# M208X.net
KiCad netlist of a schematic drawn in EAGLE
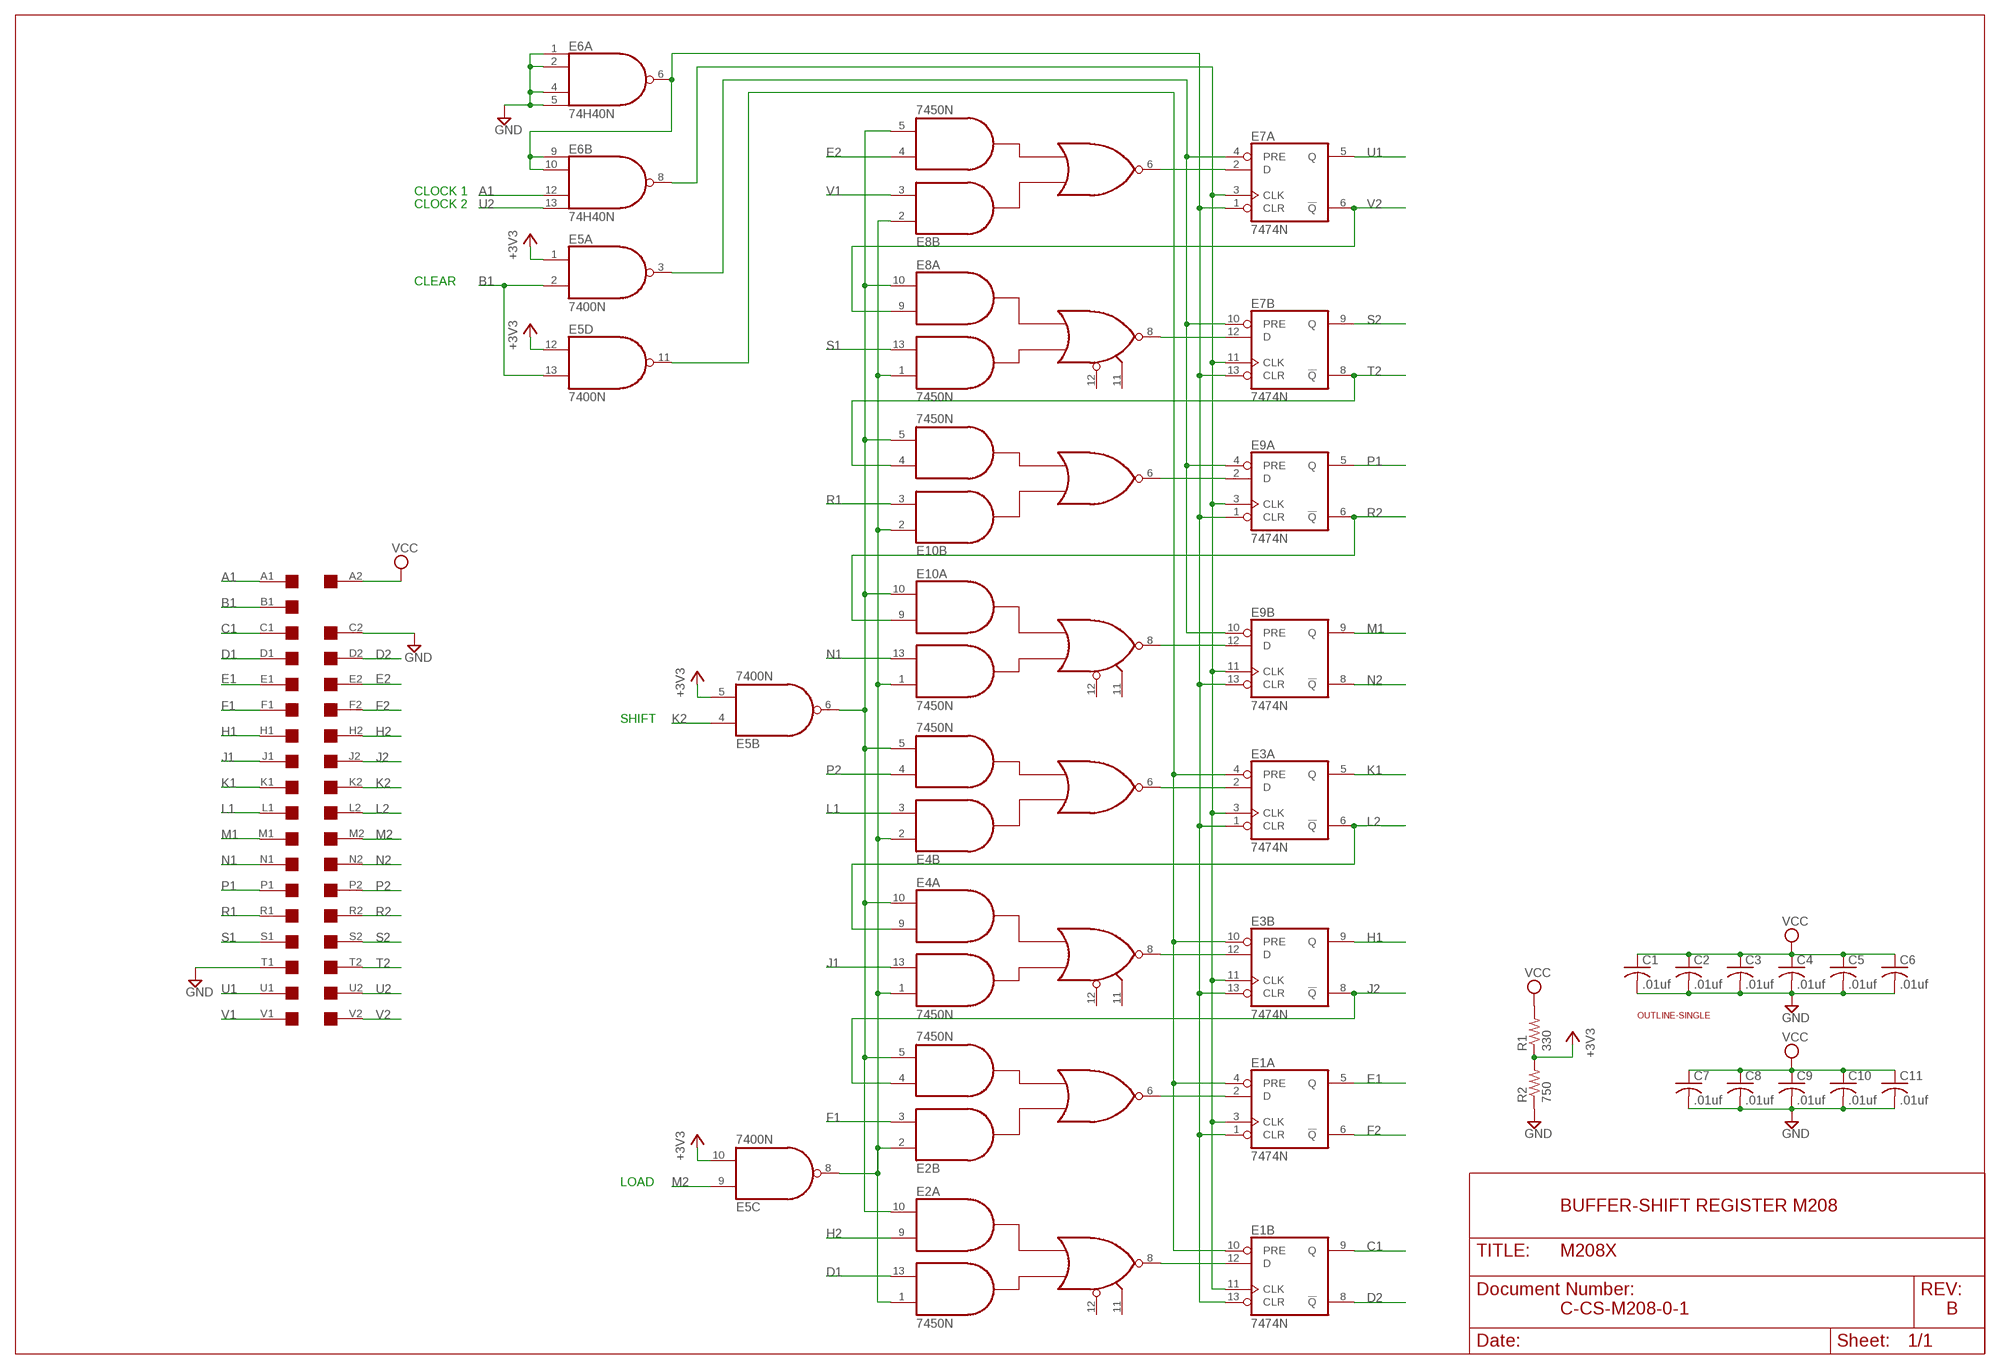
[diagram p0: schematic, sheet 1]

(export (version "E")
  (design (tool "Eeschema 10.0.6"))
  (components
    (comp (ref "C1")
      (value ".01uf")
      (footprint "eagle-import:C050-025X075")
      (libsource (lib "eagle-import") (part "C-US050-025X075"))
    )
    (comp (ref "C2")
      (value ".01uf")
      (footprint "eagle-import:C050-025X075")
      (libsource (lib "eagle-import") (part "C-US050-025X075"))
    )
    (comp (ref "C3")
      (value ".01uf")
      (footprint "eagle-import:C050-025X075")
      (libsource (lib "eagle-import") (part "C-US050-025X075"))
    )
    (comp (ref "C4")
      (value ".01uf")
      (footprint "eagle-import:C050-025X075")
      (libsource (lib "eagle-import") (part "C-US050-025X075"))
    )
    (comp (ref "C5")
      (value ".01uf")
      (footprint "eagle-import:C050-025X075")
      (libsource (lib "eagle-import") (part "C-US050-025X075"))
    )
    (comp (ref "C6")
      (value ".01uf")
      (footprint "eagle-import:C050-025X075")
      (libsource (lib "eagle-import") (part "C-US050-025X075"))
    )
    (comp (ref "C7")
      (value ".01uf")
      (footprint "eagle-import:C050-025X075")
      (libsource (lib "eagle-import") (part "C-US050-025X075"))
    )
    (comp (ref "C8")
      (value ".01uf")
      (footprint "eagle-import:C050-025X075")
      (libsource (lib "eagle-import") (part "C-US050-025X075"))
    )
    (comp (ref "C9")
      (value ".01uf")
      (footprint "eagle-import:C050-025X075")
      (libsource (lib "eagle-import") (part "C-US050-025X075"))
    )
    (comp (ref "C10")
      (value ".01uf")
      (footprint "eagle-import:C050-025X075")
      (libsource (lib "eagle-import") (part "C-US050-025X075"))
    )
    (comp (ref "C11")
      (value ".01uf")
      (footprint "eagle-import:C050-025X075")
      (libsource (lib "eagle-import") (part "C-US050-025X075"))
    )
    (comp (ref "E1")
      (value "7474N")
      (footprint "eagle-import:DIL14")
      (libsource (lib "eagle-import") (part "7474NS"))
    )
    (comp (ref "E2")
      (value "7450N")
      (footprint "eagle-import:DIL14")
      (libsource (lib "eagle-import") (part "7450N"))
    )
    (comp (ref "E3")
      (value "7474N")
      (footprint "eagle-import:DIL14")
      (libsource (lib "eagle-import") (part "7474NS"))
    )
    (comp (ref "E4")
      (value "7450N")
      (footprint "eagle-import:DIL14")
      (libsource (lib "eagle-import") (part "7450N"))
    )
    (comp (ref "E5")
      (value "7400N")
      (footprint "eagle-import:DIL14")
      (libsource (lib "eagle-import") (part "7400N"))
    )
    (comp (ref "E6")
      (value "74H40N")
      (footprint "eagle-import:DIL14")
      (libsource (lib "eagle-import") (part "7420NS"))
    )
    (comp (ref "E7")
      (value "7474N")
      (footprint "eagle-import:DIL14")
      (libsource (lib "eagle-import") (part "7474NS"))
    )
    (comp (ref "E8")
      (value "7450N")
      (footprint "eagle-import:DIL14")
      (libsource (lib "eagle-import") (part "7450N"))
    )
    (comp (ref "E9")
      (value "7474N")
      (footprint "eagle-import:DIL14")
      (libsource (lib "eagle-import") (part "7474NS"))
    )
    (comp (ref "E10")
      (value "7450N")
      (footprint "eagle-import:DIL14")
      (libsource (lib "eagle-import") (part "7450N"))
    )
    (comp (ref "R1")
      (value "330")
      (footprint "eagle-import:0207_10")
      (libsource (lib "eagle-import") (part "R-US_0207/10"))
    )
    (comp (ref "R2")
      (value "750")
      (footprint "eagle-import:0207_10")
      (libsource (lib "eagle-import") (part "R-US_0207/10"))
    )
    (comp (ref "U$1")
      (value "SINGLE")
      (footprint "eagle-import:EDGE-CON2")
      (libsource (lib "eagle-import") (part "SINGLE"))
    )
    (comp (ref "U$4")
      (value "OUTLINE-SINGLE")
      (footprint "eagle-import:SINGLE")
      (libsource (lib "eagle-import") (part "OUTLINE-SINGLE"))
    )
  )
  (nets
    (net (code "1") (name "+3V3") (class "Default")
      (node (ref "E5") (pin "1") (pinfunction "I0_1") (pintype "input"))
      (node (ref "E5") (pin "10") (pinfunction "I1_10") (pintype "input"))
      (node (ref "E5") (pin "12") (pinfunction "I0_12") (pintype "input"))
      (node (ref "E5") (pin "5") (pinfunction "I1_5") (pintype "input"))
      (node (ref "R1") (pin "1") (pinfunction "1_1") (pintype "passive"))
      (node (ref "R2") (pin "2") (pinfunction "2_2") (pintype "passive"))
    )
    (net (code "2") (name "/A1") (class "Default")
      (node (ref "E6") (pin "12") (pinfunction "I2_12") (pintype "input"))
      (node (ref "U$1") (pin "A1") (pinfunction "1_A1") (pintype "bidirectional"))
    )
    (net (code "3") (name "/B1") (class "Default")
      (node (ref "E5") (pin "13") (pinfunction "I1_13") (pintype "input"))
      (node (ref "E5") (pin "2") (pinfunction "I1_2") (pintype "input"))
      (node (ref "U$1") (pin "B1") (pinfunction "1_B1") (pintype "bidirectional"))
    )
    (net (code "4") (name "/C1") (class "Default")
      (node (ref "E1") (pin "9") (pinfunction "Q_9") (pintype "output"))
      (node (ref "U$1") (pin "C1") (pinfunction "1_C1") (pintype "bidirectional"))
    )
    (net (code "5") (name "/D1") (class "Default")
      (node (ref "E2") (pin "13") (pinfunction "I3_13") (pintype "input"))
      (node (ref "U$1") (pin "D1") (pinfunction "1_D1") (pintype "bidirectional"))
    )
    (net (code "6") (name "/D2") (class "Default")
      (node (ref "E1") (pin "8") (pinfunction "~{Q}_8") (pintype "output"))
      (node (ref "U$1") (pin "D2") (pinfunction "1_D2") (pintype "bidirectional"))
    )
    (net (code "7") (name "/E1") (class "Default")
      (node (ref "E1") (pin "5") (pinfunction "Q_5") (pintype "output"))
      (node (ref "U$1") (pin "E1") (pinfunction "1_E1") (pintype "bidirectional"))
    )
    (net (code "8") (name "/E2") (class "Default")
      (node (ref "E8") (pin "4") (pinfunction "I3_4") (pintype "input"))
      (node (ref "U$1") (pin "E2") (pinfunction "1_E2") (pintype "bidirectional"))
    )
    (net (code "9") (name "/F1") (class "Default")
      (node (ref "E2") (pin "3") (pinfunction "I2_3") (pintype "input"))
      (node (ref "U$1") (pin "F1") (pinfunction "1_F1") (pintype "bidirectional"))
    )
    (net (code "10") (name "/F2") (class "Default")
      (node (ref "E1") (pin "6") (pinfunction "~{Q}_6") (pintype "output"))
      (node (ref "U$1") (pin "F2") (pinfunction "1_F2") (pintype "bidirectional"))
    )
    (net (code "11") (name "/H1") (class "Default")
      (node (ref "E3") (pin "9") (pinfunction "Q_9") (pintype "output"))
      (node (ref "U$1") (pin "H1") (pinfunction "1_H1") (pintype "bidirectional"))
    )
    (net (code "12") (name "/H2") (class "Default")
      (node (ref "E2") (pin "9") (pinfunction "I2_9") (pintype "input"))
      (node (ref "U$1") (pin "H2") (pinfunction "1_H2") (pintype "bidirectional"))
    )
    (net (code "13") (name "/J1") (class "Default")
      (node (ref "E4") (pin "13") (pinfunction "I3_13") (pintype "input"))
      (node (ref "U$1") (pin "J1") (pinfunction "1_J1") (pintype "bidirectional"))
    )
    (net (code "14") (name "/J2") (class "Default")
      (node (ref "E2") (pin "4") (pinfunction "I3_4") (pintype "input"))
      (node (ref "E3") (pin "8") (pinfunction "~{Q}_8") (pintype "output"))
      (node (ref "U$1") (pin "J2") (pinfunction "1_J2") (pintype "bidirectional"))
    )
    (net (code "15") (name "/K1") (class "Default")
      (node (ref "E3") (pin "5") (pinfunction "Q_5") (pintype "output"))
      (node (ref "U$1") (pin "K1") (pinfunction "1_K1") (pintype "bidirectional"))
    )
    (net (code "16") (name "/K2") (class "Default")
      (node (ref "E5") (pin "4") (pinfunction "I0_4") (pintype "input"))
      (node (ref "U$1") (pin "K2") (pinfunction "1_K2") (pintype "bidirectional"))
    )
    (net (code "17") (name "/L1") (class "Default")
      (node (ref "E4") (pin "3") (pinfunction "I2_3") (pintype "input"))
      (node (ref "U$1") (pin "L1") (pinfunction "1_L1") (pintype "bidirectional"))
    )
    (net (code "18") (name "/L2") (class "Default")
      (node (ref "E3") (pin "6") (pinfunction "~{Q}_6") (pintype "output"))
      (node (ref "E4") (pin "9") (pinfunction "I2_9") (pintype "input"))
      (node (ref "U$1") (pin "L2") (pinfunction "1_L2") (pintype "bidirectional"))
    )
    (net (code "19") (name "/M1") (class "Default")
      (node (ref "E9") (pin "9") (pinfunction "Q_9") (pintype "output"))
      (node (ref "U$1") (pin "M1") (pinfunction "1_M1") (pintype "bidirectional"))
    )
    (net (code "20") (name "/M2") (class "Default")
      (node (ref "E5") (pin "9") (pinfunction "I0_9") (pintype "input"))
      (node (ref "U$1") (pin "M2") (pinfunction "1_M2") (pintype "bidirectional"))
    )
    (net (code "21") (name "/N1") (class "Default")
      (node (ref "E10") (pin "13") (pinfunction "I3_13") (pintype "input"))
      (node (ref "U$1") (pin "N1") (pinfunction "1_N1") (pintype "bidirectional"))
    )
    (net (code "22") (name "/N2") (class "Default")
      (node (ref "E9") (pin "8") (pinfunction "~{Q}_8") (pintype "output"))
      (node (ref "U$1") (pin "N2") (pinfunction "1_N2") (pintype "bidirectional"))
    )
    (net (code "23") (name "/P1") (class "Default")
      (node (ref "E9") (pin "5") (pinfunction "Q_5") (pintype "output"))
      (node (ref "U$1") (pin "P1") (pinfunction "1_P1") (pintype "bidirectional"))
    )
    (net (code "24") (name "/P2") (class "Default")
      (node (ref "E4") (pin "4") (pinfunction "I3_4") (pintype "input"))
      (node (ref "U$1") (pin "P2") (pinfunction "1_P2") (pintype "bidirectional"))
    )
    (net (code "25") (name "/R1") (class "Default")
      (node (ref "E10") (pin "3") (pinfunction "I2_3") (pintype "input"))
      (node (ref "U$1") (pin "R1") (pinfunction "1_R1") (pintype "bidirectional"))
    )
    (net (code "26") (name "/R2") (class "Default")
      (node (ref "E10") (pin "9") (pinfunction "I2_9") (pintype "input"))
      (node (ref "E9") (pin "6") (pinfunction "~{Q}_6") (pintype "output"))
      (node (ref "U$1") (pin "R2") (pinfunction "1_R2") (pintype "bidirectional"))
    )
    (net (code "27") (name "/S1") (class "Default")
      (node (ref "E8") (pin "13") (pinfunction "I3_13") (pintype "input"))
      (node (ref "U$1") (pin "S1") (pinfunction "1_S1") (pintype "bidirectional"))
    )
    (net (code "28") (name "/S2") (class "Default")
      (node (ref "E7") (pin "9") (pinfunction "Q_9") (pintype "output"))
      (node (ref "U$1") (pin "S2") (pinfunction "1_S2") (pintype "bidirectional"))
    )
    (net (code "29") (name "/T2") (class "Default")
      (node (ref "E10") (pin "4") (pinfunction "I3_4") (pintype "input"))
      (node (ref "E7") (pin "8") (pinfunction "~{Q}_8") (pintype "output"))
      (node (ref "U$1") (pin "T2") (pinfunction "1_T2") (pintype "bidirectional"))
    )
    (net (code "30") (name "/U1") (class "Default")
      (node (ref "E7") (pin "5") (pinfunction "Q_5") (pintype "output"))
      (node (ref "U$1") (pin "U1") (pinfunction "1_U1") (pintype "bidirectional"))
    )
    (net (code "31") (name "/U2") (class "Default")
      (node (ref "E6") (pin "13") (pinfunction "I3_13") (pintype "input"))
      (node (ref "U$1") (pin "U2") (pinfunction "1_U2") (pintype "bidirectional"))
    )
    (net (code "32") (name "/V1") (class "Default")
      (node (ref "E8") (pin "3") (pinfunction "I2_3") (pintype "input"))
      (node (ref "U$1") (pin "V1") (pinfunction "1_V1") (pintype "bidirectional"))
    )
    (net (code "33") (name "/V2") (class "Default")
      (node (ref "E7") (pin "6") (pinfunction "~{Q}_6") (pintype "output"))
      (node (ref "E8") (pin "9") (pinfunction "I2_9") (pintype "input"))
      (node (ref "U$1") (pin "V2") (pinfunction "1_V2") (pintype "bidirectional"))
    )
    (net (code "34") (name "GND") (class "Default")
      (node (ref "C1") (pin "2") (pinfunction "2_2") (pintype "passive"))
      (node (ref "C10") (pin "2") (pinfunction "2_2") (pintype "passive"))
      (node (ref "C11") (pin "2") (pinfunction "2_2") (pintype "passive"))
      (node (ref "C2") (pin "2") (pinfunction "2_2") (pintype "passive"))
      (node (ref "C3") (pin "2") (pinfunction "2_2") (pintype "passive"))
      (node (ref "C4") (pin "2") (pinfunction "2_2") (pintype "passive"))
      (node (ref "C5") (pin "2") (pinfunction "2_2") (pintype "passive"))
      (node (ref "C6") (pin "2") (pinfunction "2_2") (pintype "passive"))
      (node (ref "C7") (pin "2") (pinfunction "2_2") (pintype "passive"))
      (node (ref "C8") (pin "2") (pinfunction "2_2") (pintype "passive"))
      (node (ref "C9") (pin "2") (pinfunction "2_2") (pintype "passive"))
      (node (ref "E6") (pin "1") (pinfunction "I0_1") (pintype "input"))
      (node (ref "E6") (pin "2") (pinfunction "I1_2") (pintype "input"))
      (node (ref "E6") (pin "4") (pinfunction "I2_4") (pintype "input"))
      (node (ref "E6") (pin "5") (pinfunction "I3_5") (pintype "input"))
      (node (ref "R2") (pin "1") (pinfunction "1_1") (pintype "passive"))
      (node (ref "U$1") (pin "C2") (pinfunction "1_C2") (pintype "bidirectional"))
      (node (ref "U$1") (pin "T1") (pinfunction "1_T1") (pintype "bidirectional"))
    )
    (net (code "35") (name "Net-(E1A-CLK)") (class "Default")
      (node (ref "E1") (pin "11") (pinfunction "CLK_11") (pintype "input"))
      (node (ref "E1") (pin "3") (pinfunction "CLK_3") (pintype "input"))
      (node (ref "E3") (pin "11") (pinfunction "CLK_11") (pintype "input"))
      (node (ref "E3") (pin "3") (pinfunction "CLK_3") (pintype "input"))
      (node (ref "E6") (pin "8") (pinfunction "O_8") (pintype "output"))
      (node (ref "E7") (pin "11") (pinfunction "CLK_11") (pintype "input"))
      (node (ref "E7") (pin "3") (pinfunction "CLK_3") (pintype "input"))
      (node (ref "E9") (pin "11") (pinfunction "CLK_11") (pintype "input"))
      (node (ref "E9") (pin "3") (pinfunction "CLK_3") (pintype "input"))
    )
    (net (code "36") (name "Net-(E1A-CLR)") (class "Default")
      (node (ref "E1") (pin "1") (pinfunction "CLR_1") (pintype "input"))
      (node (ref "E1") (pin "13") (pinfunction "CLR_13") (pintype "input"))
      (node (ref "E3") (pin "1") (pinfunction "CLR_1") (pintype "input"))
      (node (ref "E3") (pin "13") (pinfunction "CLR_13") (pintype "input"))
      (node (ref "E6") (pin "10") (pinfunction "I1_10") (pintype "input"))
      (node (ref "E6") (pin "6") (pinfunction "O_6") (pintype "output"))
      (node (ref "E6") (pin "9") (pinfunction "I0_9") (pintype "input"))
      (node (ref "E7") (pin "1") (pinfunction "CLR_1") (pintype "input"))
      (node (ref "E7") (pin "13") (pinfunction "CLR_13") (pintype "input"))
      (node (ref "E9") (pin "1") (pinfunction "CLR_1") (pintype "input"))
      (node (ref "E9") (pin "13") (pinfunction "CLR_13") (pintype "input"))
    )
    (net (code "37") (name "Net-(E1A-D)") (class "Default")
      (node (ref "E1") (pin "2") (pinfunction "D_2") (pintype "input"))
      (node (ref "E2") (pin "6") (pinfunction "O_6") (pintype "output"))
    )
    (net (code "38") (name "Net-(E1A-PRE)") (class "Default")
      (node (ref "E1") (pin "10") (pinfunction "PRE_10") (pintype "input"))
      (node (ref "E1") (pin "4") (pinfunction "PRE_4") (pintype "input"))
      (node (ref "E3") (pin "10") (pinfunction "PRE_10") (pintype "input"))
      (node (ref "E3") (pin "4") (pinfunction "PRE_4") (pintype "input"))
      (node (ref "E5") (pin "11") (pinfunction "O_11") (pintype "output"))
    )
    (net (code "39") (name "Net-(E1B-D)") (class "Default")
      (node (ref "E1") (pin "12") (pinfunction "D_12") (pintype "input"))
      (node (ref "E2") (pin "8") (pinfunction "O_8") (pintype "output"))
    )
    (net (code "40") (name "Net-(E3A-D)") (class "Default")
      (node (ref "E3") (pin "2") (pinfunction "D_2") (pintype "input"))
      (node (ref "E4") (pin "6") (pinfunction "O_6") (pintype "output"))
    )
    (net (code "41") (name "Net-(E3B-D)") (class "Default")
      (node (ref "E3") (pin "12") (pinfunction "D_12") (pintype "input"))
      (node (ref "E4") (pin "8") (pinfunction "O_8") (pintype "output"))
    )
    (net (code "42") (name "Net-(E5A-O)") (class "Default")
      (node (ref "E5") (pin "3") (pinfunction "O_3") (pintype "output"))
      (node (ref "E7") (pin "10") (pinfunction "PRE_10") (pintype "input"))
      (node (ref "E7") (pin "4") (pinfunction "PRE_4") (pintype "input"))
      (node (ref "E9") (pin "10") (pinfunction "PRE_10") (pintype "input"))
      (node (ref "E9") (pin "4") (pinfunction "PRE_4") (pintype "input"))
    )
    (net (code "43") (name "Net-(E7A-D)") (class "Default")
      (node (ref "E7") (pin "2") (pinfunction "D_2") (pintype "input"))
      (node (ref "E8") (pin "6") (pinfunction "O_6") (pintype "output"))
    )
    (net (code "44") (name "Net-(E7B-D)") (class "Default")
      (node (ref "E7") (pin "12") (pinfunction "D_12") (pintype "input"))
      (node (ref "E8") (pin "8") (pinfunction "O_8") (pintype "output"))
    )
    (net (code "45") (name "Net-(E10A-I1)") (class "Default")
      (node (ref "E10") (pin "10") (pinfunction "I1_10") (pintype "input"))
      (node (ref "E10") (pin "5") (pinfunction "I4_5") (pintype "input"))
      (node (ref "E2") (pin "10") (pinfunction "I1_10") (pintype "input"))
      (node (ref "E2") (pin "5") (pinfunction "I4_5") (pintype "input"))
      (node (ref "E4") (pin "10") (pinfunction "I1_10") (pintype "input"))
      (node (ref "E4") (pin "5") (pinfunction "I4_5") (pintype "input"))
      (node (ref "E5") (pin "6") (pinfunction "O_6") (pintype "output"))
      (node (ref "E8") (pin "10") (pinfunction "I1_10") (pintype "input"))
      (node (ref "E8") (pin "5") (pinfunction "I4_5") (pintype "input"))
    )
    (net (code "46") (name "Net-(E10A-I4)") (class "Default")
      (node (ref "E10") (pin "1") (pinfunction "I4_1") (pintype "input"))
      (node (ref "E10") (pin "2") (pinfunction "I1_2") (pintype "input"))
      (node (ref "E2") (pin "1") (pinfunction "I4_1") (pintype "input"))
      (node (ref "E2") (pin "2") (pinfunction "I1_2") (pintype "input"))
      (node (ref "E4") (pin "1") (pinfunction "I4_1") (pintype "input"))
      (node (ref "E4") (pin "2") (pinfunction "I1_2") (pintype "input"))
      (node (ref "E5") (pin "8") (pinfunction "O_8") (pintype "output"))
      (node (ref "E8") (pin "1") (pinfunction "I4_1") (pintype "input"))
      (node (ref "E8") (pin "2") (pinfunction "I1_2") (pintype "input"))
    )
    (net (code "47") (name "Net-(E10A-O)") (class "Default")
      (node (ref "E10") (pin "8") (pinfunction "O_8") (pintype "output"))
      (node (ref "E9") (pin "12") (pinfunction "D_12") (pintype "input"))
    )
    (net (code "48") (name "Net-(E10B-O)") (class "Default")
      (node (ref "E10") (pin "6") (pinfunction "O_6") (pintype "output"))
      (node (ref "E9") (pin "2") (pinfunction "D_2") (pintype "input"))
    )
    (net (code "49") (name "VCC") (class "Default")
      (node (ref "C1") (pin "1") (pinfunction "1_1") (pintype "passive"))
      (node (ref "C10") (pin "1") (pinfunction "1_1") (pintype "passive"))
      (node (ref "C11") (pin "1") (pinfunction "1_1") (pintype "passive"))
      (node (ref "C2") (pin "1") (pinfunction "1_1") (pintype "passive"))
      (node (ref "C3") (pin "1") (pinfunction "1_1") (pintype "passive"))
      (node (ref "C4") (pin "1") (pinfunction "1_1") (pintype "passive"))
      (node (ref "C5") (pin "1") (pinfunction "1_1") (pintype "passive"))
      (node (ref "C6") (pin "1") (pinfunction "1_1") (pintype "passive"))
      (node (ref "C7") (pin "1") (pinfunction "1_1") (pintype "passive"))
      (node (ref "C8") (pin "1") (pinfunction "1_1") (pintype "passive"))
      (node (ref "C9") (pin "1") (pinfunction "1_1") (pintype "passive"))
      (node (ref "R1") (pin "2") (pinfunction "2_2") (pintype "passive"))
      (node (ref "U$1") (pin "A2") (pinfunction "1_A2") (pintype "bidirectional"))
    )
    (net (code "50") (name "unconnected-(E2A-I5-Pad12)") (class "Default")
      (node (ref "E2") (pin "12") (pinfunction "I5_12") (pintype "passive"))
    )
    (net (code "51") (name "unconnected-(E2A-I6-Pad11)") (class "Default")
      (node (ref "E2") (pin "11") (pinfunction "I6_11") (pintype "passive"))
    )
    (net (code "52") (name "unconnected-(E4A-I5-Pad12)") (class "Default")
      (node (ref "E4") (pin "12") (pinfunction "I5_12") (pintype "passive"))
    )
    (net (code "53") (name "unconnected-(E4A-I6-Pad11)") (class "Default")
      (node (ref "E4") (pin "11") (pinfunction "I6_11") (pintype "passive"))
    )
    (net (code "54") (name "unconnected-(E8A-I5-Pad12)") (class "Default")
      (node (ref "E8") (pin "12") (pinfunction "I5_12") (pintype "passive"))
    )
    (net (code "55") (name "unconnected-(E8A-I6-Pad11)") (class "Default")
      (node (ref "E8") (pin "11") (pinfunction "I6_11") (pintype "passive"))
    )
    (net (code "56") (name "unconnected-(E10A-I5-Pad12)") (class "Default")
      (node (ref "E10") (pin "12") (pinfunction "I5_12") (pintype "passive"))
    )
    (net (code "57") (name "unconnected-(E10A-I6-Pad11)") (class "Default")
      (node (ref "E10") (pin "11") (pinfunction "I6_11") (pintype "passive"))
    )
  )
)
